# SCH_555-Circuit_2025-03-21.net
KiCad netlist of a schematic drawn in EasyEDA
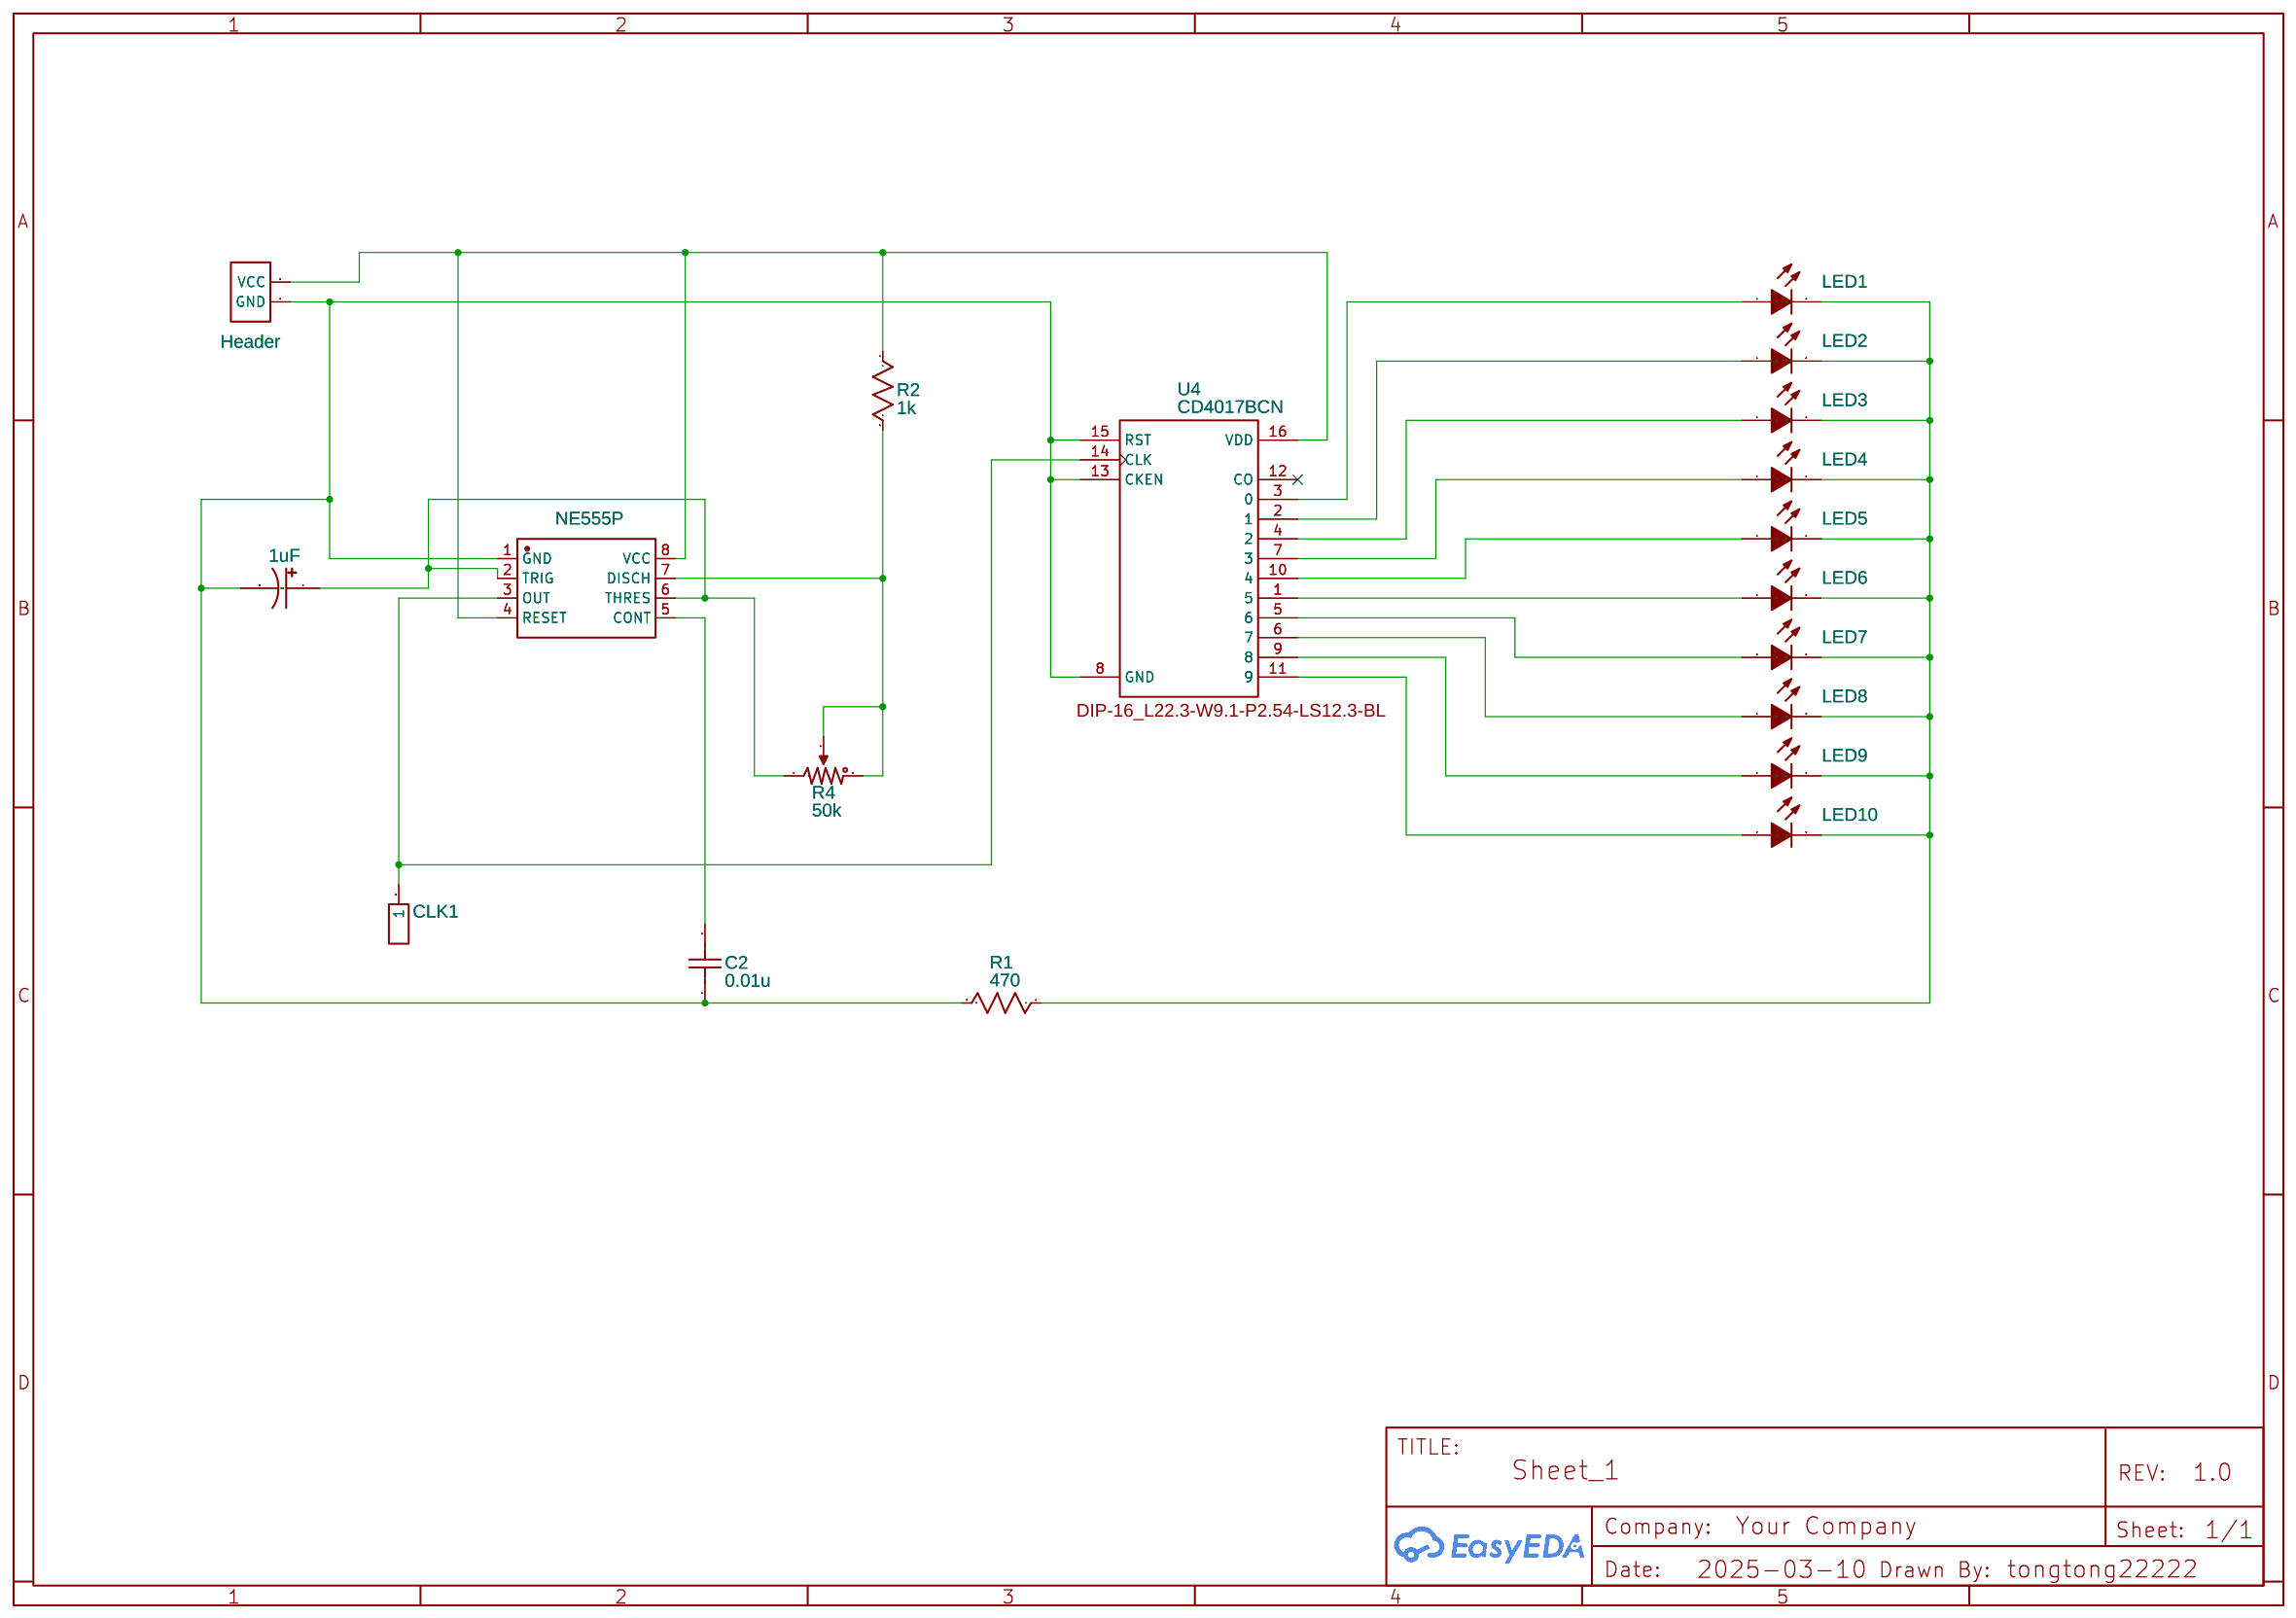
[diagram p0: schematic sheet]

(export (version "E")
  (design (tool "Eeschema 10.0.6"))
  (components
    (comp (ref "C1")
      (value "1uF")
      (fields (field (name "Manufacturer Part") "UVZ1H010MDD") (field (name "Manufacturer") "Nichicon(尼吉康)"))
      (libsource (lib "") (part "UVZ1H010MDD"))
    )
    (comp (ref "C2") (value "0.01u") (libsource (lib "") (part "C_0603_US")))
    (comp (ref "CLK1")
      (value "C81276")
      (fields
        (field (name "Manufacturer Part") "2.54-1*1P针")
        (field (name "Manufacturer") "BOOMELE(Boom Precision Elec)")
      )
      (libsource (lib "") (part "Header-Male-2.54_1x1"))
    )
    (comp (ref "H1") (value "Header") (libsource (lib "") (part "HEADER-FEMALE-2.54_1X2")))
    (comp (ref "LED1") (value "LED_5MM") (libsource (lib "") (part "LED_5MM")))
    (comp (ref "LED2") (value "LED_5MM") (libsource (lib "") (part "LED_5MM")))
    (comp (ref "LED3") (value "LED_5MM") (libsource (lib "") (part "LED_5MM")))
    (comp (ref "LED4") (value "LED_5MM") (libsource (lib "") (part "LED_5MM")))
    (comp (ref "LED5") (value "LED_5MM") (libsource (lib "") (part "LED_5MM")))
    (comp (ref "LED6") (value "LED_5MM") (libsource (lib "") (part "LED_5MM")))
    (comp (ref "LED7") (value "LED_5MM") (libsource (lib "") (part "LED_5MM")))
    (comp (ref "LED8") (value "LED_5MM") (libsource (lib "") (part "LED_5MM")))
    (comp (ref "LED9") (value "LED_5MM") (libsource (lib "") (part "LED_5MM")))
    (comp (ref "LED10") (value "LED_5MM") (libsource (lib "") (part "LED_5MM")))
    (comp (ref "R1")
      (value "470")
      (fields (field (name "Manufacturer Part") "?"))
      (libsource (lib "") (part "Resistor"))
    )
    (comp (ref "R2")
      (value "1k")
      (fields (field (name "Manufacturer Part") "?"))
      (libsource (lib "") (part "Resistor_1"))
    )
    (comp (ref "R4")
      (value "50k")
      (fields (field (name "Manufacturer Part") "?"))
      (libsource (lib "") (part "Potentiometer"))
    )
    (comp (ref "U2")
      (value "NE555P")
      (fields (field (name "Manufacturer") "TI(德州仪器)"))
      (libsource (lib "") (part "NE555P"))
    )
    (comp (ref "U4") (value "CD4017BCN") (libsource (lib "") (part "CD4017BCN")))
  )
  (nets
    (net (code "1") (name "Net-(H1-GND)") (class "Default")
      (node (ref "C1") (pin "2") (pinfunction "2_2") (pintype "unspecified"))
      (node (ref "C2") (pin "1") (pinfunction "1_1") (pintype "unspecified"))
      (node (ref "H1") (pin "2") (pinfunction "GND_2") (pintype "unspecified"))
      (node (ref "R1") (pin "2") (pinfunction "2_2") (pintype "unspecified"))
      (node (ref "U2") (pin "1") (pinfunction "GND_1") (pintype "unspecified"))
      (node (ref "U4") (pin "13") (pinfunction "CKEN_13") (pintype "unspecified"))
      (node (ref "U4") (pin "15") (pinfunction "RST_15") (pintype "unspecified"))
      (node (ref "U4") (pin "8") (pinfunction "GND_8") (pintype "passive"))
    )
    (net (code "2") (name "Net-(H1-VCC)") (class "Default")
      (node (ref "H1") (pin "1") (pinfunction "VCC_1") (pintype "unspecified"))
      (node (ref "R2") (pin "1") (pinfunction "1_1") (pintype "unspecified"))
      (node (ref "U2") (pin "4") (pinfunction "RESET_4") (pintype "unspecified"))
      (node (ref "U2") (pin "8") (pinfunction "VCC_8") (pintype "unspecified"))
      (node (ref "U4") (pin "16") (pinfunction "VDD_16") (pintype "passive"))
    )
    (net (code "3") (name "Net-(LED1-A)") (class "Default")
      (node (ref "LED1") (pin "1") (pinfunction "A_1") (pintype "input"))
      (node (ref "U4") (pin "3") (pinfunction "0_3") (pintype "output"))
    )
    (net (code "4") (name "Net-(LED1-K)") (class "Default")
      (node (ref "LED1") (pin "2") (pinfunction "K_2") (pintype "input"))
      (node (ref "LED10") (pin "2") (pinfunction "K_2") (pintype "input"))
      (node (ref "LED2") (pin "2") (pinfunction "K_2") (pintype "input"))
      (node (ref "LED3") (pin "2") (pinfunction "K_2") (pintype "input"))
      (node (ref "LED4") (pin "2") (pinfunction "K_2") (pintype "input"))
      (node (ref "LED5") (pin "2") (pinfunction "K_2") (pintype "input"))
      (node (ref "LED6") (pin "2") (pinfunction "K_2") (pintype "input"))
      (node (ref "LED7") (pin "2") (pinfunction "K_2") (pintype "input"))
      (node (ref "LED8") (pin "2") (pinfunction "K_2") (pintype "input"))
      (node (ref "LED9") (pin "2") (pinfunction "K_2") (pintype "input"))
      (node (ref "R1") (pin "1") (pinfunction "1_1") (pintype "unspecified"))
    )
    (net (code "5") (name "Net-(LED2-A)") (class "Default")
      (node (ref "LED2") (pin "1") (pinfunction "A_1") (pintype "input"))
      (node (ref "U4") (pin "2") (pinfunction "1_2") (pintype "output"))
    )
    (net (code "6") (name "Net-(LED3-A)") (class "Default")
      (node (ref "LED3") (pin "1") (pinfunction "A_1") (pintype "input"))
      (node (ref "U4") (pin "4") (pinfunction "2_4") (pintype "output"))
    )
    (net (code "7") (name "Net-(LED4-A)") (class "Default")
      (node (ref "LED4") (pin "1") (pinfunction "A_1") (pintype "input"))
      (node (ref "U4") (pin "7") (pinfunction "3_7") (pintype "output"))
    )
    (net (code "8") (name "Net-(LED5-A)") (class "Default")
      (node (ref "LED5") (pin "1") (pinfunction "A_1") (pintype "input"))
      (node (ref "U4") (pin "10") (pinfunction "4_10") (pintype "output"))
    )
    (net (code "9") (name "Net-(LED6-A)") (class "Default")
      (node (ref "LED6") (pin "1") (pinfunction "A_1") (pintype "input"))
      (node (ref "U4") (pin "1") (pinfunction "5_1") (pintype "output"))
    )
    (net (code "10") (name "Net-(LED7-A)") (class "Default")
      (node (ref "LED7") (pin "1") (pinfunction "A_1") (pintype "input"))
      (node (ref "U4") (pin "5") (pinfunction "6_5") (pintype "output"))
    )
    (net (code "11") (name "Net-(LED8-A)") (class "Default")
      (node (ref "LED8") (pin "1") (pinfunction "A_1") (pintype "input"))
      (node (ref "U4") (pin "6") (pinfunction "7_6") (pintype "output"))
    )
    (net (code "12") (name "Net-(LED9-A)") (class "Default")
      (node (ref "LED9") (pin "1") (pinfunction "A_1") (pintype "input"))
      (node (ref "U4") (pin "9") (pinfunction "8_9") (pintype "output"))
    )
    (net (code "13") (name "Net-(LED10-A)") (class "Default")
      (node (ref "LED10") (pin "1") (pinfunction "A_1") (pintype "input"))
      (node (ref "U4") (pin "11") (pinfunction "9_11") (pintype "output"))
    )
    (net (code "14") (name "Net-(R4-2)") (class "Default")
      (node (ref "R2") (pin "2") (pinfunction "2_2") (pintype "unspecified"))
      (node (ref "R4") (pin "2") (pinfunction "3_2") (pintype "unspecified"))
      (node (ref "R4") (pin "3") (pinfunction "2_3") (pintype "unspecified"))
      (node (ref "U2") (pin "7") (pinfunction "DISCH_7") (pintype "unspecified"))
    )
    (net (code "15") (name "Net-(U2-CONT)") (class "Default")
      (node (ref "C2") (pin "2") (pinfunction "2_2") (pintype "unspecified"))
      (node (ref "U2") (pin "5") (pinfunction "CONT_5") (pintype "unspecified"))
    )
    (net (code "16") (name "Net-(U2-OUT)") (class "Default")
      (node (ref "CLK1") (pin "1") (pinfunction "1_1") (pintype "unspecified"))
      (node (ref "U2") (pin "3") (pinfunction "OUT_3") (pintype "unspecified"))
      (node (ref "U4") (pin "14") (pinfunction "CLK_14") (pintype "unspecified"))
    )
    (net (code "17") (name "Net-(U2-THRES)") (class "Default")
      (node (ref "C1") (pin "1") (pinfunction "1_1") (pintype "unspecified"))
      (node (ref "R4") (pin "1") (pinfunction "1_1") (pintype "unspecified"))
      (node (ref "U2") (pin "2") (pinfunction "TRIG_2") (pintype "unspecified"))
      (node (ref "U2") (pin "6") (pinfunction "THRES_6") (pintype "unspecified"))
    )
    (net (code "18") (name "unconnected-(U4-CO-Pad12)") (class "Default")
      (node (ref "U4") (pin "12") (pinfunction "CO_12") (pintype "output+no_connect"))
    )
  )
)
